# CM_USB.net
KiCad netlist of a schematic drawn in Altium Designer
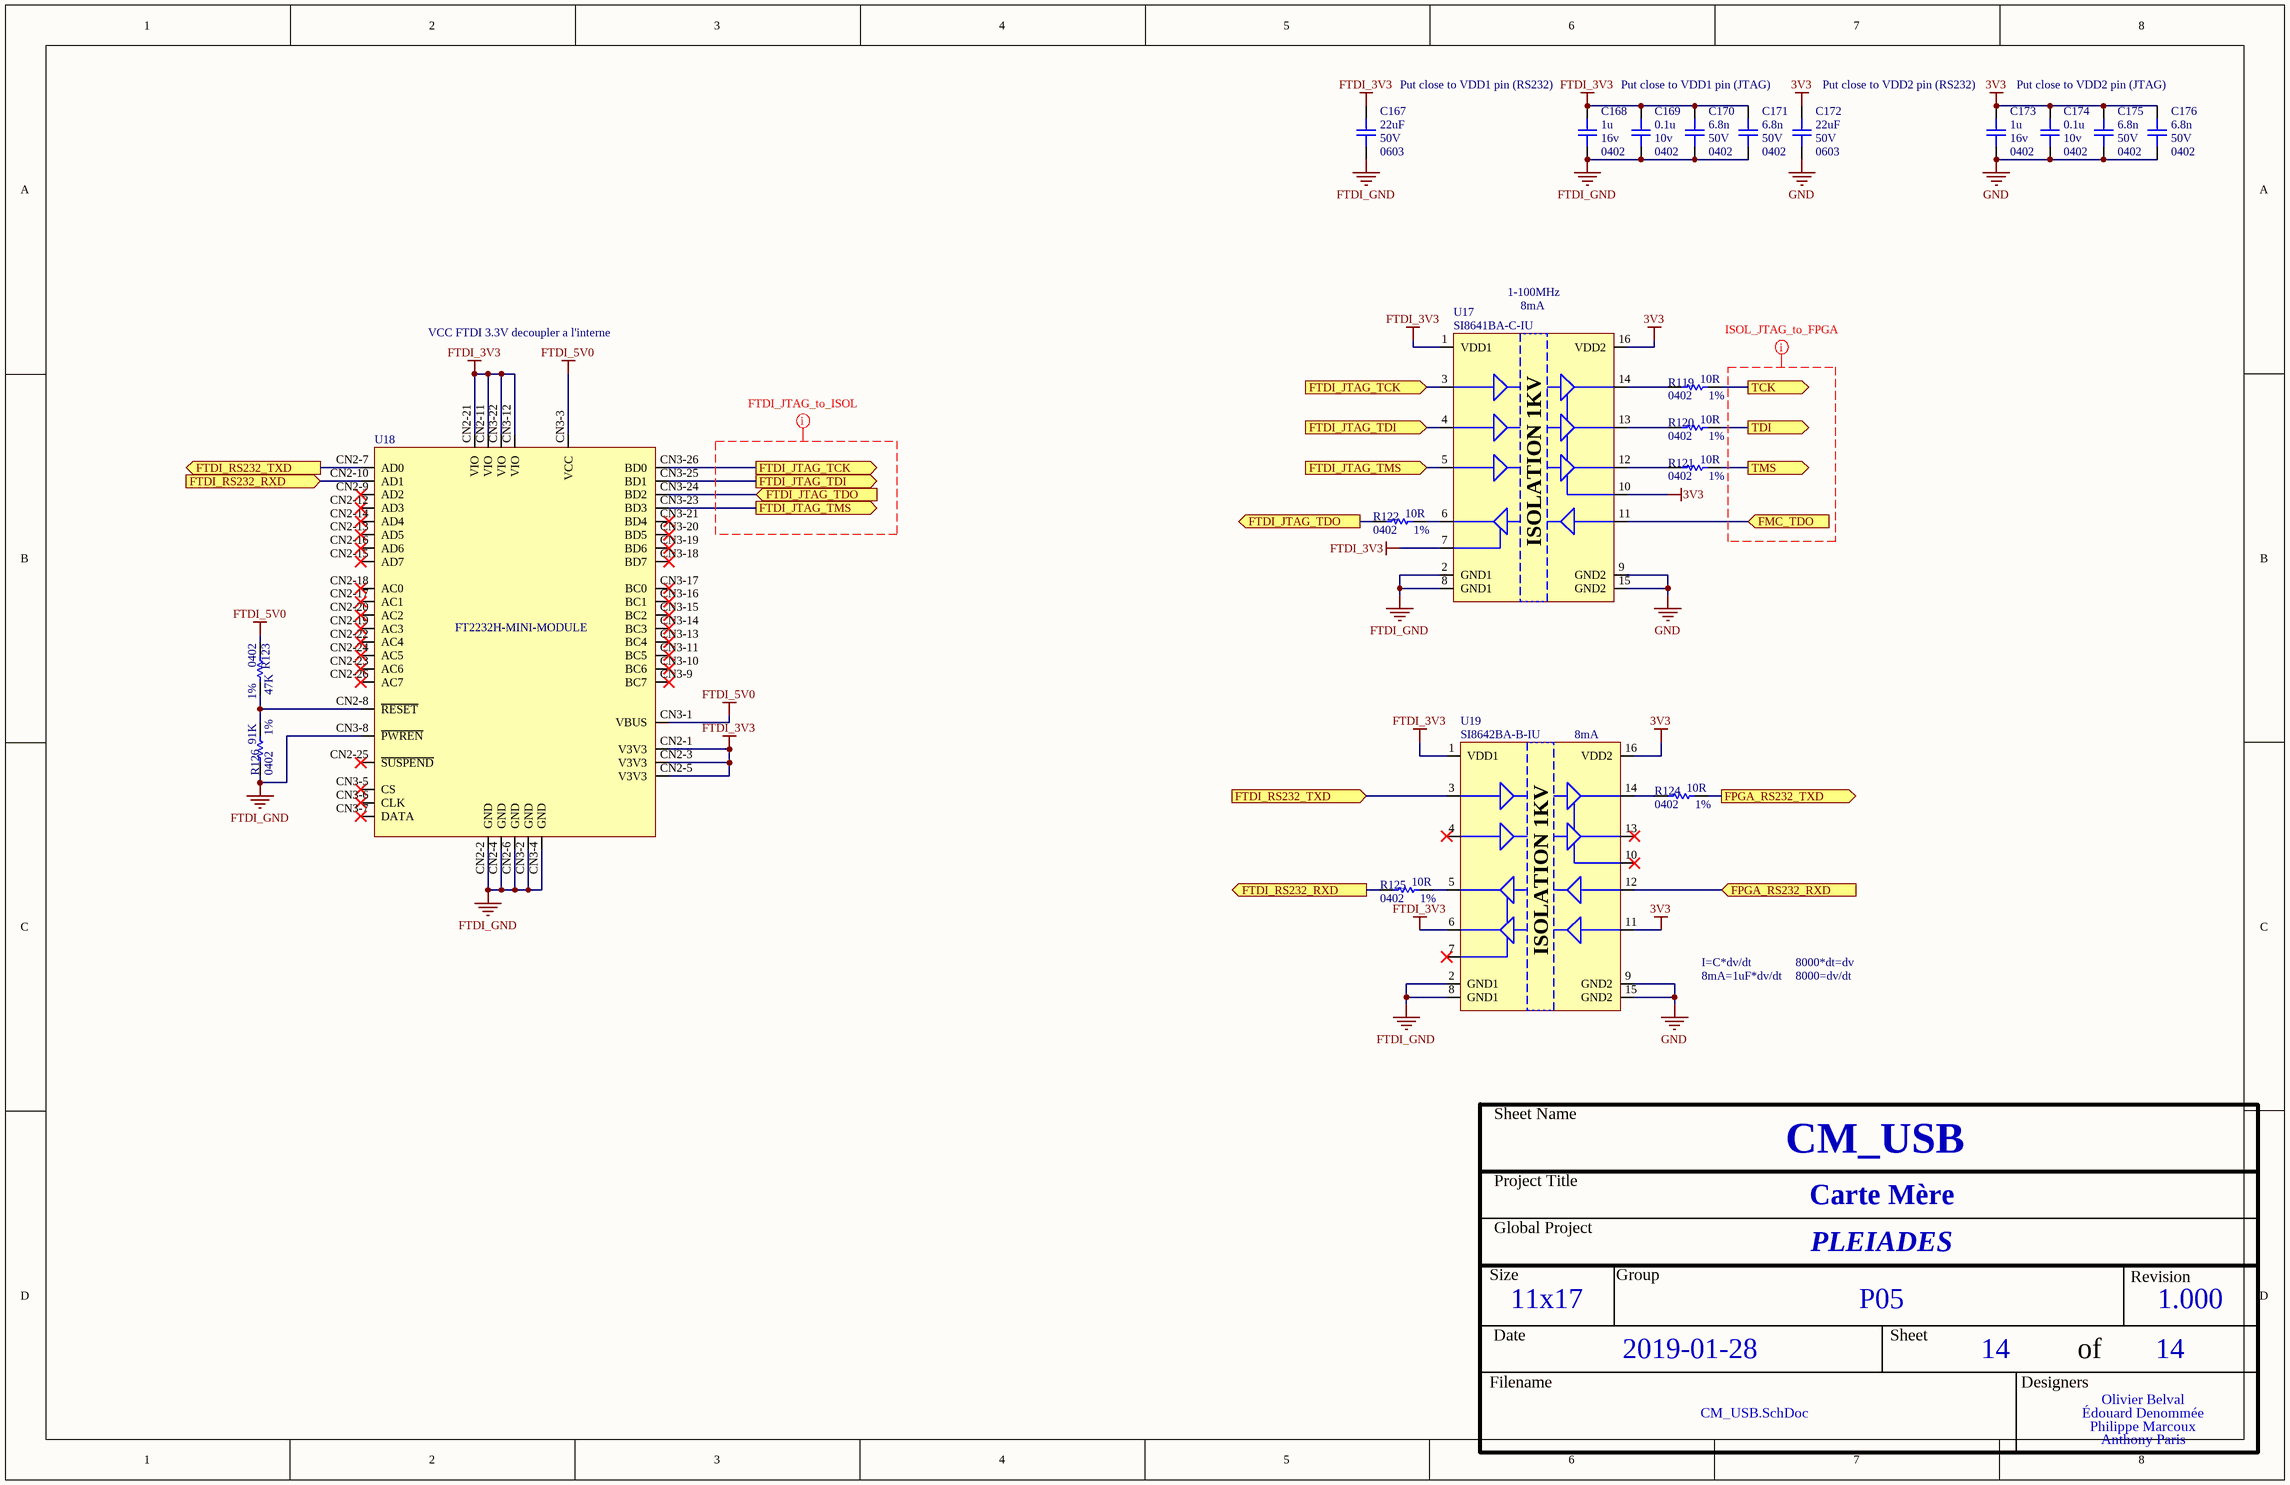
[diagram p0: CM_USB.SchDoc]

(export (version "E")
  (design (tool "Eeschema 10.0.6"))
  (components
    (comp (ref "C167")
      (value "22uF")
      (footprint "CAP_0402")
      (description "CAP - 0402")
      (fields
        (field (name "VOLTAGE") "50V")
        (field (name "PACKAGE") "0603")
        (field (name "CREATEDBY") "Jonathan Bouchard")
      )
      (libsource (lib "S7CAS_Lib2019_REV1_00") (part "CAP - 0402"))
    )
    (comp (ref "C168")
      (value "1u")
      (footprint "CAP_0402")
      (description "CAP - 0402")
      (fields
        (field (name "VOLTAGE") "16v")
        (field (name "PACKAGE") "0402")
        (field (name "CREATEDBY") "Jonathan Bouchard")
      )
      (libsource (lib "S7CAS_Lib2019_REV1_00") (part "CAP - 0402"))
    )
    (comp (ref "C169")
      (value "0.1u")
      (footprint "CAP_0402")
      (description "CAP - 0402")
      (fields
        (field (name "VOLTAGE") "10v")
        (field (name "PACKAGE") "0402")
        (field (name "CREATEDBY") "Jonathan Bouchard")
      )
      (libsource (lib "S7CAS_Lib2019_REV1_00") (part "CAP - 0402"))
    )
    (comp (ref "C170")
      (value "6.8n")
      (footprint "CAP_0402")
      (description "CAP - 0402")
      (fields
        (field (name "VOLTAGE") "50V")
        (field (name "PACKAGE") "0402")
        (field (name "CREATEDBY") "Jonathan Bouchard")
      )
      (libsource (lib "S7CAS_Lib2019_REV1_00") (part "CAP - 0402"))
    )
    (comp (ref "C171")
      (value "6.8n")
      (footprint "CAP_0402")
      (description "CAP - 0402")
      (fields
        (field (name "VOLTAGE") "50V")
        (field (name "PACKAGE") "0402")
        (field (name "CREATEDBY") "Jonathan Bouchard")
      )
      (libsource (lib "S7CAS_Lib2019_REV1_00") (part "CAP - 0402"))
    )
    (comp (ref "C172")
      (value "22uF")
      (footprint "CAP_0402")
      (description "CAP - 0402")
      (fields
        (field (name "VOLTAGE") "50V")
        (field (name "PACKAGE") "0603")
        (field (name "CREATEDBY") "Jonathan Bouchard")
      )
      (libsource (lib "S7CAS_Lib2019_REV1_00") (part "CAP - 0402"))
    )
    (comp (ref "C173")
      (value "1u")
      (footprint "CAP_0402")
      (description "CAP - 0402")
      (fields
        (field (name "VOLTAGE") "16v")
        (field (name "PACKAGE") "0402")
        (field (name "CREATEDBY") "Jonathan Bouchard")
      )
      (libsource (lib "S7CAS_Lib2019_REV1_00") (part "CAP - 0402"))
    )
    (comp (ref "C174")
      (value "0.1u")
      (footprint "CAP_0402")
      (description "CAP - 0402")
      (fields
        (field (name "VOLTAGE") "10v")
        (field (name "PACKAGE") "0402")
        (field (name "CREATEDBY") "Jonathan Bouchard")
      )
      (libsource (lib "S7CAS_Lib2019_REV1_00") (part "CAP - 0402"))
    )
    (comp (ref "C175")
      (value "6.8n")
      (footprint "CAP_0402")
      (description "CAP - 0402")
      (fields
        (field (name "VOLTAGE") "50V")
        (field (name "PACKAGE") "0402")
        (field (name "CREATEDBY") "Jonathan Bouchard")
      )
      (libsource (lib "S7CAS_Lib2019_REV1_00") (part "CAP - 0402"))
    )
    (comp (ref "C176")
      (value "6.8n")
      (footprint "CAP_0402")
      (description "CAP - 0402")
      (fields
        (field (name "VOLTAGE") "50V")
        (field (name "PACKAGE") "0402")
        (field (name "CREATEDBY") "Jonathan Bouchard")
      )
      (libsource (lib "S7CAS_Lib2019_REV1_00") (part "CAP - 0402"))
    )
    (comp (ref "R119")
      (value "10R")
      (footprint "RES_0402")
      (description "RES - 0402")
      (fields
        (field (name "VOLTAGE") "50V")
        (field (name "POWER") "1/16W")
        (field (name "PACKAGE") "0402")
        (field (name "PRECISION") "1%")
        (field (name "CREATEDBY") "Jonathan Bouchard")
      )
      (libsource (lib "S7CAS_Lib2019_REV1_00") (part "RES - 0402"))
    )
    (comp (ref "R120")
      (value "10R")
      (footprint "RES_0402")
      (description "RES - 0402")
      (fields
        (field (name "VOLTAGE") "50V")
        (field (name "POWER") "1/16W")
        (field (name "PACKAGE") "0402")
        (field (name "PRECISION") "1%")
        (field (name "CREATEDBY") "Jonathan Bouchard")
      )
      (libsource (lib "S7CAS_Lib2019_REV1_00") (part "RES - 0402"))
    )
    (comp (ref "R121")
      (value "10R")
      (footprint "RES_0402")
      (description "RES - 0402")
      (fields
        (field (name "VOLTAGE") "50V")
        (field (name "POWER") "1/16W")
        (field (name "PACKAGE") "0402")
        (field (name "PRECISION") "1%")
        (field (name "CREATEDBY") "Jonathan Bouchard")
      )
      (libsource (lib "S7CAS_Lib2019_REV1_00") (part "RES - 0402"))
    )
    (comp (ref "R122")
      (value "10R")
      (footprint "RES_0402")
      (description "RES - 0402")
      (fields
        (field (name "VOLTAGE") "50V")
        (field (name "POWER") "1/16W")
        (field (name "PACKAGE") "0402")
        (field (name "PRECISION") "1%")
        (field (name "CREATEDBY") "Jonathan Bouchard")
      )
      (libsource (lib "S7CAS_Lib2019_REV1_00") (part "RES - 0402"))
    )
    (comp (ref "R123")
      (value "47K")
      (footprint "RES_0402")
      (description "RES - 0402")
      (fields
        (field (name "VOLTAGE") "50V")
        (field (name "POWER") "1/16W")
        (field (name "PACKAGE") "0402")
        (field (name "PRECISION") "1%")
        (field (name "CREATEDBY") "Jonathan Bouchard")
      )
      (libsource (lib "S7CAS_Lib2019_REV1_00") (part "RES - 0402"))
    )
    (comp (ref "R124")
      (value "10R")
      (footprint "RES_0402")
      (description "RES - 0402")
      (fields
        (field (name "VOLTAGE") "50V")
        (field (name "POWER") "1/16W")
        (field (name "PACKAGE") "0402")
        (field (name "PRECISION") "1%")
        (field (name "CREATEDBY") "Jonathan Bouchard")
      )
      (libsource (lib "S7CAS_Lib2019_REV1_00") (part "RES - 0402"))
    )
    (comp (ref "R125")
      (value "10R")
      (footprint "RES_0402")
      (description "RES - 0402")
      (fields
        (field (name "VOLTAGE") "50V")
        (field (name "POWER") "1/16W")
        (field (name "PACKAGE") "0402")
        (field (name "PRECISION") "1%")
        (field (name "CREATEDBY") "Jonathan Bouchard")
      )
      (libsource (lib "S7CAS_Lib2019_REV1_00") (part "RES - 0402"))
    )
    (comp (ref "R126")
      (value "91K")
      (footprint "RES_0402")
      (description "RES - 0402")
      (fields
        (field (name "VOLTAGE") "50V")
        (field (name "POWER") "1/16W")
        (field (name "PACKAGE") "0402")
        (field (name "PRECISION") "1%")
        (field (name "CREATEDBY") "Jonathan Bouchard")
      )
      (libsource (lib "S7CAS_Lib2019_REV1_00") (part "RES - 0402"))
    )
    (comp (ref "U17")
      (value "SI8641BA-C-IU")
      (footprint "ISO_SI8642BA-B-IU")
      (description "ISO - DIGITAL ISOLATOR 1KV 4CH 3:1 GEN PURP -  SOP-16")
      (fields
        (field (name "VOLTAGE") "2.5 V ~ 5.5 V")
        (field (name "MFG") "Silicon Labs")
        (field (name "CREATEDBY") "Jonathan Bouchard")
      )
      (libsource (lib "S7CAS_Lib2019_REV1_00") (part "ISO_SI8641BA-C-IU"))
    )
    (comp (ref "U18")
      (value "FT2232H-MINI-MODULE")
      (footprint "COM_USB_FT2232H-MINI-MODULE")
      (description "COM - USB FTDI FT2232H Mini-Module - TH")
      (fields (field (name "MFG") "Micrel") (field (name "CREATEDBY") "Jonathan Bouchard"))
      (libsource (lib "S7CAS_Lib2017") (part "COM_USB_FT2232H-MINI-MODULE"))
    )
    (comp (ref "U19")
      (value "SI8642BA-B-IU")
      (footprint "ISO_SI8642BA-B-IU")
      (description "ISO - DIGITAL ISOLATOR 1KV 4CH 2:2 GEN PURP -  SOP-16")
      (fields
        (field (name "VOLTAGE") "2.5 V ~ 5.5 V")
        (field (name "MFG") "Silicon Labs")
        (field (name "CREATEDBY") "Jonathan Bouchard")
      )
      (libsource (lib "S7CAS_Lib2017") (part "ISO_SI8642BA-B-IU"))
    )
  )
  (nets
    (net (code "1") (name "/FMC_TDO") (class "Default")
      (node (ref "U17") (pin "11") (pinfunction "B4_11") (pintype "passive"))
    )
    (net (code "2") (name "/FPGA_RS232_RXD") (class "Default")
      (node (ref "U19") (pin "12") (pinfunction "B3_12") (pintype "passive"))
    )
    (net (code "3") (name "/FPGA_RS232_TXD") (class "Default")
      (node (ref "R124") (pin "2") (pinfunction "2_2") (pintype "passive"))
    )
    (net (code "4") (name "/FTDI_JTAG_TCK") (class "Default")
      (node (ref "U17") (pin "3") (pinfunction "A1_3") (pintype "passive"))
      (node (ref "U18") (pin "CN3-26") (pinfunction "BD0_CN3-26") (pintype "passive"))
    )
    (net (code "5") (name "/FTDI_JTAG_TDI") (class "Default")
      (node (ref "U17") (pin "4") (pinfunction "A2_4") (pintype "passive"))
      (node (ref "U18") (pin "CN3-25") (pinfunction "BD1_CN3-25") (pintype "passive"))
    )
    (net (code "6") (name "/FTDI_JTAG_TDO") (class "Default")
      (node (ref "R122") (pin "1") (pinfunction "1_1") (pintype "passive"))
      (node (ref "U18") (pin "CN3-24") (pinfunction "BD2_CN3-24") (pintype "passive"))
    )
    (net (code "7") (name "/FTDI_JTAG_TMS") (class "Default")
      (node (ref "U17") (pin "5") (pinfunction "A3_5") (pintype "passive"))
      (node (ref "U18") (pin "CN3-23") (pinfunction "BD3_CN3-23") (pintype "passive"))
    )
    (net (code "8") (name "/FTDI_RS232_RXD") (class "Default")
      (node (ref "R125") (pin "1") (pinfunction "1_1") (pintype "passive"))
      (node (ref "U18") (pin "CN2-10") (pinfunction "AD1_CN2-10") (pintype "passive"))
    )
    (net (code "9") (name "/FTDI_RS232_TXD") (class "Default")
      (node (ref "U18") (pin "CN2-7") (pinfunction "AD0_CN2-7") (pintype "passive"))
      (node (ref "U19") (pin "3") (pinfunction "A1_3") (pintype "passive"))
    )
    (net (code "10") (name "/TCK") (class "Default")
      (node (ref "R119") (pin "2") (pinfunction "2_2") (pintype "passive"))
    )
    (net (code "11") (name "/TDI") (class "Default")
      (node (ref "R121") (pin "2") (pinfunction "2_2") (pintype "passive"))
    )
    (net (code "12") (name "/TMS") (class "Default")
      (node (ref "R120") (pin "2") (pinfunction "2_2") (pintype "passive"))
    )
    (net (code "13") (name "3V3") (class "Default")
      (node (ref "C172") (pin "2") (pinfunction "2_2") (pintype "passive"))
      (node (ref "C173") (pin "2") (pinfunction "2_2") (pintype "passive"))
      (node (ref "C174") (pin "2") (pinfunction "2_2") (pintype "passive"))
      (node (ref "C175") (pin "2") (pinfunction "2_2") (pintype "passive"))
      (node (ref "C176") (pin "2") (pinfunction "2_2") (pintype "passive"))
      (node (ref "U17") (pin "10") (pinfunction "EN2_10") (pintype "passive"))
      (node (ref "U17") (pin "16") (pinfunction "VDD2_16") (pintype "power_in"))
      (node (ref "U19") (pin "11") (pinfunction "B4_11") (pintype "passive"))
      (node (ref "U19") (pin "16") (pinfunction "VDD2_16") (pintype "power_in"))
    )
    (net (code "14") (name "FTDI_3V3") (class "Default")
      (node (ref "C167") (pin "2") (pinfunction "2_2") (pintype "passive"))
      (node (ref "C168") (pin "2") (pinfunction "2_2") (pintype "passive"))
      (node (ref "C169") (pin "2") (pinfunction "2_2") (pintype "passive"))
      (node (ref "C170") (pin "2") (pinfunction "2_2") (pintype "passive"))
      (node (ref "C171") (pin "2") (pinfunction "2_2") (pintype "passive"))
      (node (ref "U17") (pin "1") (pinfunction "VDD1_1") (pintype "power_in"))
      (node (ref "U17") (pin "7") (pinfunction "EN1_7") (pintype "passive"))
      (node (ref "U18") (pin "CN2-1") (pinfunction "V3V3_CN2-1") (pintype "power_in"))
      (node (ref "U18") (pin "CN2-11") (pinfunction "VIO_CN2-11") (pintype "passive"))
      (node (ref "U18") (pin "CN2-21") (pinfunction "VIO_CN2-21") (pintype "passive"))
      (node (ref "U18") (pin "CN2-3") (pinfunction "V3V3_CN2-3") (pintype "power_in"))
      (node (ref "U18") (pin "CN2-5") (pinfunction "V3V3_CN2-5") (pintype "power_in"))
      (node (ref "U18") (pin "CN3-12") (pinfunction "VIO_CN3-12") (pintype "passive"))
      (node (ref "U18") (pin "CN3-22") (pinfunction "VIO_CN3-22") (pintype "passive"))
      (node (ref "U19") (pin "1") (pinfunction "VDD1_1") (pintype "power_in"))
      (node (ref "U19") (pin "6") (pinfunction "A4_6") (pintype "passive"))
    )
    (net (code "15") (name "FTDI_5V0") (class "Default")
      (node (ref "R123") (pin "1") (pinfunction "1_1") (pintype "passive"))
      (node (ref "U18") (pin "CN3-1") (pinfunction "VBUS_CN3-1") (pintype "passive"))
      (node (ref "U18") (pin "CN3-3") (pinfunction "VCC_CN3-3") (pintype "power_in"))
    )
    (net (code "16") (name "FTDI_GND") (class "Default")
      (node (ref "C167") (pin "1") (pinfunction "1_1") (pintype "passive"))
      (node (ref "C168") (pin "1") (pinfunction "1_1") (pintype "passive"))
      (node (ref "C169") (pin "1") (pinfunction "1_1") (pintype "passive"))
      (node (ref "C170") (pin "1") (pinfunction "1_1") (pintype "passive"))
      (node (ref "C171") (pin "1") (pinfunction "1_1") (pintype "passive"))
      (node (ref "R126") (pin "1") (pinfunction "1_1") (pintype "passive"))
      (node (ref "U17") (pin "2") (pinfunction "GND1_2") (pintype "passive"))
      (node (ref "U17") (pin "8") (pinfunction "GND1_8") (pintype "passive"))
      (node (ref "U18") (pin "CN2-2") (pinfunction "GND_CN2-2") (pintype "passive"))
      (node (ref "U18") (pin "CN2-4") (pinfunction "GND_CN2-4") (pintype "passive"))
      (node (ref "U18") (pin "CN2-6") (pinfunction "GND_CN2-6") (pintype "passive"))
      (node (ref "U18") (pin "CN3-2") (pinfunction "GND_CN3-2") (pintype "passive"))
      (node (ref "U18") (pin "CN3-4") (pinfunction "GND_CN3-4") (pintype "passive"))
      (node (ref "U18") (pin "CN3-8") (pinfunction "PWREN_CN3-8") (pintype "passive"))
      (node (ref "U19") (pin "2") (pinfunction "GND1_2") (pintype "passive"))
      (node (ref "U19") (pin "8") (pinfunction "GND1_8") (pintype "passive"))
    )
    (net (code "17") (name "GND") (class "Default")
      (node (ref "C172") (pin "1") (pinfunction "1_1") (pintype "passive"))
      (node (ref "C173") (pin "1") (pinfunction "1_1") (pintype "passive"))
      (node (ref "C174") (pin "1") (pinfunction "1_1") (pintype "passive"))
      (node (ref "C175") (pin "1") (pinfunction "1_1") (pintype "passive"))
      (node (ref "C176") (pin "1") (pinfunction "1_1") (pintype "passive"))
      (node (ref "U17") (pin "15") (pinfunction "GND2_15") (pintype "passive"))
      (node (ref "U17") (pin "9") (pinfunction "GND2_9") (pintype "passive"))
      (node (ref "U19") (pin "15") (pinfunction "GND2_15") (pintype "passive"))
      (node (ref "U19") (pin "9") (pinfunction "GND2_9") (pintype "passive"))
    )
    (net (code "18") (name "Net-(U17-A4)") (class "Default")
      (node (ref "R122") (pin "2") (pinfunction "2_2") (pintype "passive"))
      (node (ref "U17") (pin "6") (pinfunction "A4_6") (pintype "passive"))
    )
    (net (code "19") (name "Net-(U17-B1)") (class "Default")
      (node (ref "R119") (pin "1") (pinfunction "1_1") (pintype "passive"))
      (node (ref "U17") (pin "14") (pinfunction "B1_14") (pintype "passive"))
    )
    (net (code "20") (name "Net-(U17-B2)") (class "Default")
      (node (ref "R121") (pin "1") (pinfunction "1_1") (pintype "passive"))
      (node (ref "U17") (pin "13") (pinfunction "B2_13") (pintype "passive"))
    )
    (net (code "21") (name "Net-(U17-B3)") (class "Default")
      (node (ref "R120") (pin "1") (pinfunction "1_1") (pintype "passive"))
      (node (ref "U17") (pin "12") (pinfunction "B3_12") (pintype "passive"))
    )
    (net (code "22") (name "Net-(U18-RESET)") (class "Default")
      (node (ref "R123") (pin "2") (pinfunction "2_2") (pintype "passive"))
      (node (ref "R126") (pin "2") (pinfunction "2_2") (pintype "passive"))
      (node (ref "U18") (pin "CN2-8") (pinfunction "RESET_CN2-8") (pintype "passive"))
    )
    (net (code "23") (name "Net-(U19-A3)") (class "Default")
      (node (ref "R125") (pin "2") (pinfunction "2_2") (pintype "passive"))
      (node (ref "U19") (pin "5") (pinfunction "A3_5") (pintype "passive"))
    )
    (net (code "24") (name "Net-(U19-B1)") (class "Default")
      (node (ref "R124") (pin "1") (pinfunction "1_1") (pintype "passive"))
      (node (ref "U19") (pin "14") (pinfunction "B1_14") (pintype "passive"))
    )
    (net (code "25") (name "unconnected-(U18-AC0-PadCN2-18)") (class "Default")
      (node (ref "U18") (pin "CN2-18") (pinfunction "AC0_CN2-18") (pintype "passive+no_connect"))
    )
    (net (code "26") (name "unconnected-(U18-AC1-PadCN2-17)") (class "Default")
      (node (ref "U18") (pin "CN2-17") (pinfunction "AC1_CN2-17") (pintype "passive+no_connect"))
    )
    (net (code "27") (name "unconnected-(U18-AC2-PadCN2-20)") (class "Default")
      (node (ref "U18") (pin "CN2-20") (pinfunction "AC2_CN2-20") (pintype "passive+no_connect"))
    )
    (net (code "28") (name "unconnected-(U18-AC3-PadCN2-19)") (class "Default")
      (node (ref "U18") (pin "CN2-19") (pinfunction "AC3_CN2-19") (pintype "passive+no_connect"))
    )
    (net (code "29") (name "unconnected-(U18-AC4-PadCN2-22)") (class "Default")
      (node (ref "U18") (pin "CN2-22") (pinfunction "AC4_CN2-22") (pintype "passive+no_connect"))
    )
    (net (code "30") (name "unconnected-(U18-AC5-PadCN2-24)") (class "Default")
      (node (ref "U18") (pin "CN2-24") (pinfunction "AC5_CN2-24") (pintype "passive+no_connect"))
    )
    (net (code "31") (name "unconnected-(U18-AC6-PadCN2-23)") (class "Default")
      (node (ref "U18") (pin "CN2-23") (pinfunction "AC6_CN2-23") (pintype "passive+no_connect"))
    )
    (net (code "32") (name "unconnected-(U18-AC7-PadCN2-26)") (class "Default")
      (node (ref "U18") (pin "CN2-26") (pinfunction "AC7_CN2-26") (pintype "passive+no_connect"))
    )
    (net (code "33") (name "unconnected-(U18-AD2-PadCN2-9)") (class "Default")
      (node (ref "U18") (pin "CN2-9") (pinfunction "AD2_CN2-9") (pintype "passive+no_connect"))
    )
    (net (code "34") (name "unconnected-(U18-AD3-PadCN2-12)") (class "Default")
      (node (ref "U18") (pin "CN2-12") (pinfunction "AD3_CN2-12") (pintype "passive+no_connect"))
    )
    (net (code "35") (name "unconnected-(U18-AD4-PadCN2-14)") (class "Default")
      (node (ref "U18") (pin "CN2-14") (pinfunction "AD4_CN2-14") (pintype "passive+no_connect"))
    )
    (net (code "36") (name "unconnected-(U18-AD5-PadCN2-13)") (class "Default")
      (node (ref "U18") (pin "CN2-13") (pinfunction "AD5_CN2-13") (pintype "passive+no_connect"))
    )
    (net (code "37") (name "unconnected-(U18-AD6-PadCN2-16)") (class "Default")
      (node (ref "U18") (pin "CN2-16") (pinfunction "AD6_CN2-16") (pintype "passive+no_connect"))
    )
    (net (code "38") (name "unconnected-(U18-AD7-PadCN2-15)") (class "Default")
      (node (ref "U18") (pin "CN2-15") (pinfunction "AD7_CN2-15") (pintype "passive+no_connect"))
    )
    (net (code "39") (name "unconnected-(U18-BC0-PadCN3-17)") (class "Default")
      (node (ref "U18") (pin "CN3-17") (pinfunction "BC0_CN3-17") (pintype "passive+no_connect"))
    )
    (net (code "40") (name "unconnected-(U18-BC1-PadCN3-16)") (class "Default")
      (node (ref "U18") (pin "CN3-16") (pinfunction "BC1_CN3-16") (pintype "passive+no_connect"))
    )
    (net (code "41") (name "unconnected-(U18-BC2-PadCN3-15)") (class "Default")
      (node (ref "U18") (pin "CN3-15") (pinfunction "BC2_CN3-15") (pintype "passive+no_connect"))
    )
    (net (code "42") (name "unconnected-(U18-BC3-PadCN3-14)") (class "Default")
      (node (ref "U18") (pin "CN3-14") (pinfunction "BC3_CN3-14") (pintype "passive+no_connect"))
    )
    (net (code "43") (name "unconnected-(U18-BC4-PadCN3-13)") (class "Default")
      (node (ref "U18") (pin "CN3-13") (pinfunction "BC4_CN3-13") (pintype "passive+no_connect"))
    )
    (net (code "44") (name "unconnected-(U18-BC5-PadCN3-11)") (class "Default")
      (node (ref "U18") (pin "CN3-11") (pinfunction "BC5_CN3-11") (pintype "passive+no_connect"))
    )
    (net (code "45") (name "unconnected-(U18-BC6-PadCN3-10)") (class "Default")
      (node (ref "U18") (pin "CN3-10") (pinfunction "BC6_CN3-10") (pintype "passive+no_connect"))
    )
    (net (code "46") (name "unconnected-(U18-BC7-PadCN3-9)") (class "Default")
      (node (ref "U18") (pin "CN3-9") (pinfunction "BC7_CN3-9") (pintype "passive+no_connect"))
    )
    (net (code "47") (name "unconnected-(U18-BD4-PadCN3-21)") (class "Default")
      (node (ref "U18") (pin "CN3-21") (pinfunction "BD4_CN3-21") (pintype "passive+no_connect"))
    )
    (net (code "48") (name "unconnected-(U18-BD5-PadCN3-20)") (class "Default")
      (node (ref "U18") (pin "CN3-20") (pinfunction "BD5_CN3-20") (pintype "passive+no_connect"))
    )
    (net (code "49") (name "unconnected-(U18-BD6-PadCN3-19)") (class "Default")
      (node (ref "U18") (pin "CN3-19") (pinfunction "BD6_CN3-19") (pintype "passive+no_connect"))
    )
    (net (code "50") (name "unconnected-(U18-BD7-PadCN3-18)") (class "Default")
      (node (ref "U18") (pin "CN3-18") (pinfunction "BD7_CN3-18") (pintype "passive+no_connect"))
    )
    (net (code "51") (name "unconnected-(U18-CLK-PadCN3-6)") (class "Default")
      (node (ref "U18") (pin "CN3-6") (pinfunction "CLK_CN3-6") (pintype "passive+no_connect"))
    )
    (net (code "52") (name "unconnected-(U18-CS-PadCN3-5)") (class "Default")
      (node (ref "U18") (pin "CN3-5") (pinfunction "CS_CN3-5") (pintype "passive+no_connect"))
    )
    (net (code "53") (name "unconnected-(U18-DATA-PadCN3-7)") (class "Default")
      (node (ref "U18") (pin "CN3-7") (pinfunction "DATA_CN3-7") (pintype "passive+no_connect"))
    )
    (net (code "54") (name "unconnected-(U18-SUSPEND-PadCN2-25)") (class "Default")
      (node (ref "U18") (pin "CN2-25") (pinfunction "SUSPEND_CN2-25") (pintype "passive+no_connect"))
    )
    (net (code "55") (name "unconnected-(U19-A2-Pad4)") (class "Default")
      (node (ref "U19") (pin "4") (pinfunction "A2_4") (pintype "passive+no_connect"))
    )
    (net (code "56") (name "unconnected-(U19-B2-Pad13)") (class "Default")
      (node (ref "U19") (pin "13") (pinfunction "B2_13") (pintype "passive+no_connect"))
    )
    (net (code "57") (name "unconnected-(U19-EN1-Pad7)") (class "Default")
      (node (ref "U19") (pin "7") (pinfunction "EN1_7") (pintype "passive+no_connect"))
    )
    (net (code "58") (name "unconnected-(U19-EN2-Pad10)") (class "Default")
      (node (ref "U19") (pin "10") (pinfunction "EN2_10") (pintype "passive+no_connect"))
    )
  )
)
